# SCH_videoplayer_2022-01-02-EASYEDA.net
KiCad netlist of a schematic drawn in EasyEDA
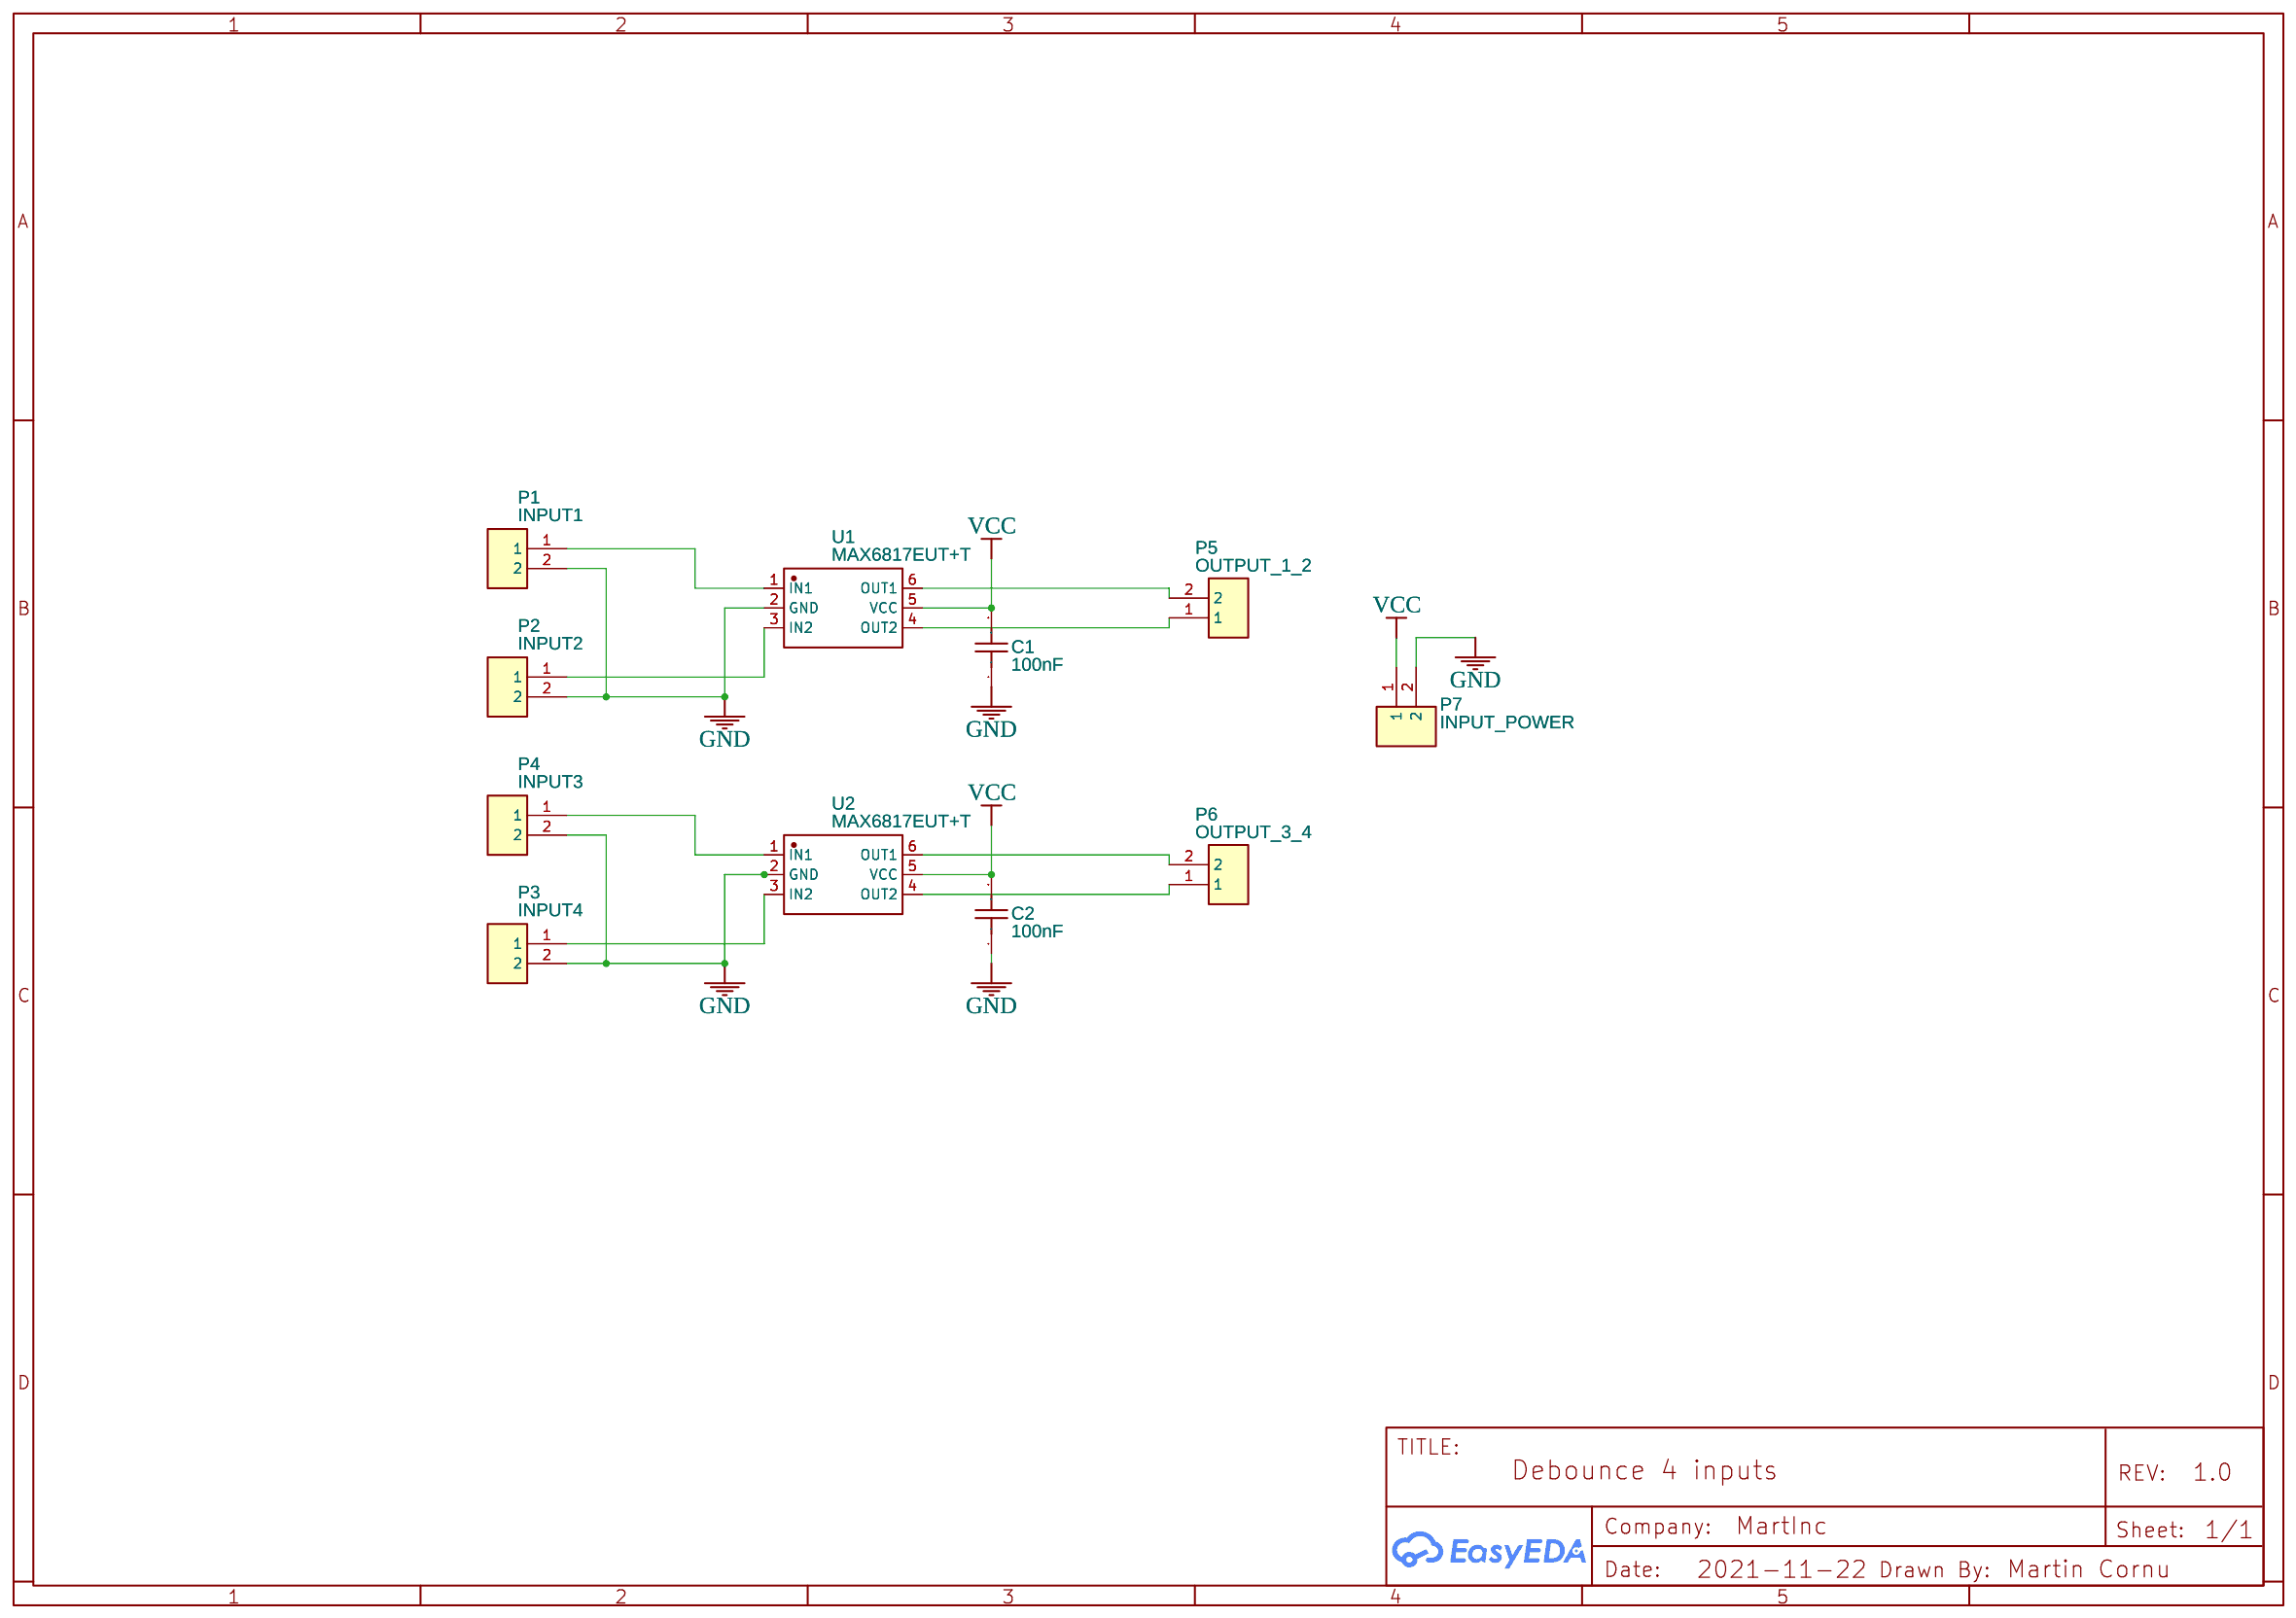
[diagram p0: schematic sheet]

(export (version "E")
  (design (tool "Eeschema 10.0.6"))
  (components
    (comp (ref "C1")
      (value "100nF")
      (fields
        (field (name "BOM_Manufacturer Part") "GRM155R61C104KA88D")
        (field (name "BOM_Supplier Part") "C77005")
      )
      (libsource (lib "") (part "GRM155R61C104KA88D"))
    )
    (comp (ref "C2")
      (value "100nF")
      (fields
        (field (name "BOM_Manufacturer Part") "GRM155R61C104KA88D")
        (field (name "BOM_Supplier Part") "C77005")
      )
      (libsource (lib "") (part "GRM155R61C104KA88D"))
    )
    (comp (ref "P1")
      (value "INPUT1")
      (fields (field (name "BOM_Supplier Part") "undefined"))
      (libsource (lib "") (part "TERMINAL_2P_5MM"))
    )
    (comp (ref "P2")
      (value "INPUT2")
      (fields (field (name "BOM_Supplier Part") "undefined"))
      (libsource (lib "") (part "TERMINAL_2P_5MM"))
    )
    (comp (ref "P3")
      (value "INPUT4")
      (fields (field (name "BOM_Supplier Part") "undefined"))
      (libsource (lib "") (part "TERMINAL_2P_5MM"))
    )
    (comp (ref "P4")
      (value "INPUT3")
      (fields (field (name "BOM_Supplier Part") "undefined"))
      (libsource (lib "") (part "TERMINAL_2P_5MM"))
    )
    (comp (ref "P5")
      (value "OUTPUT_1_2")
      (fields (field (name "BOM_Supplier Part") "undefined"))
      (libsource (lib "") (part "TERMINAL_2P_5MM_1"))
    )
    (comp (ref "P6")
      (value "OUTPUT_3_4")
      (fields (field (name "BOM_Supplier Part") "undefined"))
      (libsource (lib "") (part "TERMINAL_2P_5MM_1"))
    )
    (comp (ref "P7")
      (value "INPUT_POWER")
      (fields (field (name "BOM_Supplier Part") "undefined"))
      (libsource (lib "") (part "TERMINAL_2P_5MM_2"))
    )
    (comp (ref "U1")
      (value "MAX6817EUT+T")
      (fields (field (name "BOM_Supplier Part") "C516788"))
      (libsource (lib "") (part "MAX6817EUT+T"))
    )
    (comp (ref "U2")
      (value "MAX6817EUT+T")
      (fields (field (name "BOM_Supplier Part") "C516788"))
      (libsource (lib "") (part "MAX6817EUT+T"))
    )
  )
  (nets
    (net (code "1") (name "GND") (class "Default")
      (node (ref "C1") (pin "1") (pinfunction "1_1") (pintype "unspecified"))
      (node (ref "C2") (pin "1") (pinfunction "1_1") (pintype "unspecified"))
      (node (ref "P1") (pin "2") (pinfunction "2_2") (pintype "unspecified"))
      (node (ref "P2") (pin "2") (pinfunction "2_2") (pintype "unspecified"))
      (node (ref "P3") (pin "2") (pinfunction "2_2") (pintype "unspecified"))
      (node (ref "P4") (pin "2") (pinfunction "2_2") (pintype "unspecified"))
      (node (ref "P7") (pin "2") (pinfunction "2_2") (pintype "unspecified"))
      (node (ref "U1") (pin "2") (pinfunction "GND_2") (pintype "unspecified"))
      (node (ref "U2") (pin "2") (pinfunction "GND_2") (pintype "unspecified"))
    )
    (net (code "2") (name "Net-(U1-IN1)") (class "Default")
      (node (ref "P1") (pin "1") (pinfunction "1_1") (pintype "unspecified"))
      (node (ref "U1") (pin "1") (pinfunction "IN1_1") (pintype "unspecified"))
    )
    (net (code "3") (name "Net-(U1-IN2)") (class "Default")
      (node (ref "P2") (pin "1") (pinfunction "1_1") (pintype "unspecified"))
      (node (ref "U1") (pin "3") (pinfunction "IN2_3") (pintype "unspecified"))
    )
    (net (code "4") (name "Net-(U1-OUT1)") (class "Default")
      (node (ref "P5") (pin "2") (pinfunction "2_2") (pintype "unspecified"))
      (node (ref "U1") (pin "6") (pinfunction "OUT1_6") (pintype "unspecified"))
    )
    (net (code "5") (name "Net-(U1-OUT2)") (class "Default")
      (node (ref "P5") (pin "1") (pinfunction "1_1") (pintype "unspecified"))
      (node (ref "U1") (pin "4") (pinfunction "OUT2_4") (pintype "unspecified"))
    )
    (net (code "6") (name "Net-(U2-IN1)") (class "Default")
      (node (ref "P4") (pin "1") (pinfunction "1_1") (pintype "unspecified"))
      (node (ref "U2") (pin "1") (pinfunction "IN1_1") (pintype "unspecified"))
    )
    (net (code "7") (name "Net-(U2-IN2)") (class "Default")
      (node (ref "P3") (pin "1") (pinfunction "1_1") (pintype "unspecified"))
      (node (ref "U2") (pin "3") (pinfunction "IN2_3") (pintype "unspecified"))
    )
    (net (code "8") (name "Net-(U2-OUT1)") (class "Default")
      (node (ref "P6") (pin "2") (pinfunction "2_2") (pintype "unspecified"))
      (node (ref "U2") (pin "6") (pinfunction "OUT1_6") (pintype "unspecified"))
    )
    (net (code "9") (name "Net-(U2-OUT2)") (class "Default")
      (node (ref "P6") (pin "1") (pinfunction "1_1") (pintype "unspecified"))
      (node (ref "U2") (pin "4") (pinfunction "OUT2_4") (pintype "unspecified"))
    )
    (net (code "10") (name "VCC") (class "Default")
      (node (ref "C1") (pin "2") (pinfunction "2_2") (pintype "unspecified"))
      (node (ref "C2") (pin "2") (pinfunction "2_2") (pintype "unspecified"))
      (node (ref "P7") (pin "1") (pinfunction "1_1") (pintype "unspecified"))
      (node (ref "U1") (pin "5") (pinfunction "VCC_5") (pintype "unspecified"))
      (node (ref "U2") (pin "5") (pinfunction "VCC_5") (pintype "unspecified"))
    )
  )
)
